# POWER.net
KiCad netlist of a schematic drawn in Altium Designer
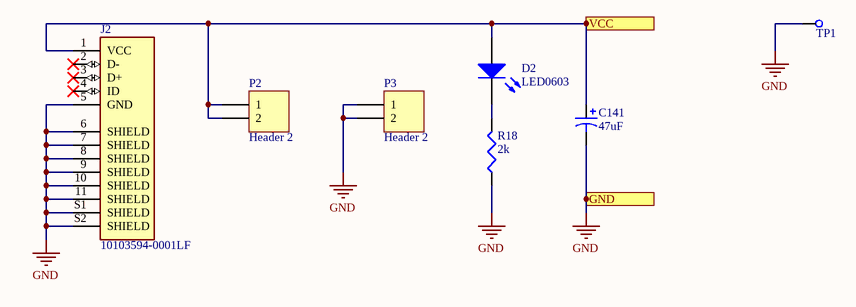
[diagram p0: POWER.SchDoc]

(export (version "E")
  (design (tool "Eeschema 10.0.6"))
  (components
    (comp (ref "C141")
      (value "47uF")
      (footprint "CAP_TANT_1206_POL")
      (description "Polarized Cap, Size 1206 Imperial (3216 Metric), Tantalum")
      (libsource (lib "LCR") (part "CAP_TANT_1206"))
    )
    (comp (ref "D2")
      (value "LED0603")
      (footprint "LED-SMD-0603")
      (description "LED 0603")
      (libsource (lib "LCR") (part "LED0603"))
    )
    (comp (ref "J2")
      (value "10103594-0001LF")
      (footprint "Connectors:AMPHENOL_10103594-0001LF")
      (description "USB - micro B USB 2.0 Receptacle Connector 5 Position Surface Mount, Right Angle; Through Hole")
      (fields (field (name "MF") "Amphenol ICC (FCI)"))
      (libsource (lib "Connectors") (part "10103594-0001LF"))
    )
    (comp (ref "P2")
      (value "Header 2")
      (footprint "HDR1X2")
      (description "Header, 2-Pin")
      (fields (field (name "PUBLISHER") "Altium Limited"))
      (libsource (lib "Miscellaneous Connectors") (part "Header 2"))
    )
    (comp (ref "P3")
      (value "Header 2")
      (footprint "HDR1X2")
      (description "Header, 2-Pin")
      (fields (field (name "PUBLISHER") "Altium Limited"))
      (libsource (lib "Miscellaneous Connectors") (part "Header 2"))
    )
    (comp (ref "R18")
      (value "2k")
      (footprint "SMD-0402")
      (description "Resistor-0402")
      (libsource (lib "LCR") (part "RES0402"))
    )
    (comp (ref "TP1")
      (value "TSW-101-15-T-S")
      (footprint "TSW-101-15-T-S")
      (description "CONN HEADER VERT 1POS")
      (libsource (lib "Connectors") (part "TSW-101-15-T-S"))
    )
  )
  (nets
    (net (code "1") (name "/VCC") (class "Default")
      (node (ref "C141") (pin "1") (pinfunction "1_1") (pintype "passive"))
      (node (ref "D2") (pin "1") (pinfunction "A_1") (pintype "passive"))
      (node (ref "J2") (pin "1") (pinfunction "VCC_1") (pintype "power_in"))
      (node (ref "P2") (pin "1") (pinfunction "1_1") (pintype "passive"))
      (node (ref "P2") (pin "2") (pinfunction "2_2") (pintype "passive"))
    )
    (net (code "2") (name "GND") (class "Default")
      (node (ref "C141") (pin "2") (pinfunction "2_2") (pintype "passive"))
      (node (ref "J2") (pin "10") (pinfunction "SHIELD_10") (pintype "passive"))
      (node (ref "J2") (pin "11") (pinfunction "SHIELD_11") (pintype "passive"))
      (node (ref "J2") (pin "5") (pinfunction "GND_5") (pintype "power_in"))
      (node (ref "J2") (pin "6") (pinfunction "SHIELD_6") (pintype "passive"))
      (node (ref "J2") (pin "7") (pinfunction "SHIELD_7") (pintype "passive"))
      (node (ref "J2") (pin "8") (pinfunction "SHIELD_8") (pintype "passive"))
      (node (ref "J2") (pin "9") (pinfunction "SHIELD_9") (pintype "passive"))
      (node (ref "J2") (pin "S1") (pinfunction "SHIELD_S1") (pintype "passive"))
      (node (ref "J2") (pin "S2") (pinfunction "SHIELD_S2") (pintype "passive"))
      (node (ref "P3") (pin "1") (pinfunction "1_1") (pintype "passive"))
      (node (ref "P3") (pin "2") (pinfunction "2_2") (pintype "passive"))
      (node (ref "R18") (pin "1") (pinfunction "1_1") (pintype "passive"))
      (node (ref "TP1") (pin "1") (pinfunction "1_1") (pintype "passive"))
    )
    (net (code "3") (name "Net-(D2-K)") (class "Default")
      (node (ref "D2") (pin "2") (pinfunction "K_2") (pintype "passive"))
      (node (ref "R18") (pin "2") (pinfunction "2_2") (pintype "passive"))
    )
    (net (code "4") (name "unconnected-(J2-D+-Pad3)") (class "Default")
      (node (ref "J2") (pin "3") (pinfunction "D+_3") (pintype "bidirectional+no_connect"))
    )
    (net (code "5") (name "unconnected-(J2-D--Pad2)") (class "Default")
      (node (ref "J2") (pin "2") (pinfunction "D-_2") (pintype "bidirectional+no_connect"))
    )
    (net (code "6") (name "unconnected-(J2-ID-Pad4)") (class "Default")
      (node (ref "J2") (pin "4") (pinfunction "ID_4") (pintype "bidirectional+no_connect"))
    )
  )
)
